# SparkFun_MAX30101_Qwiic.net
KiCad netlist of a schematic drawn in EAGLE
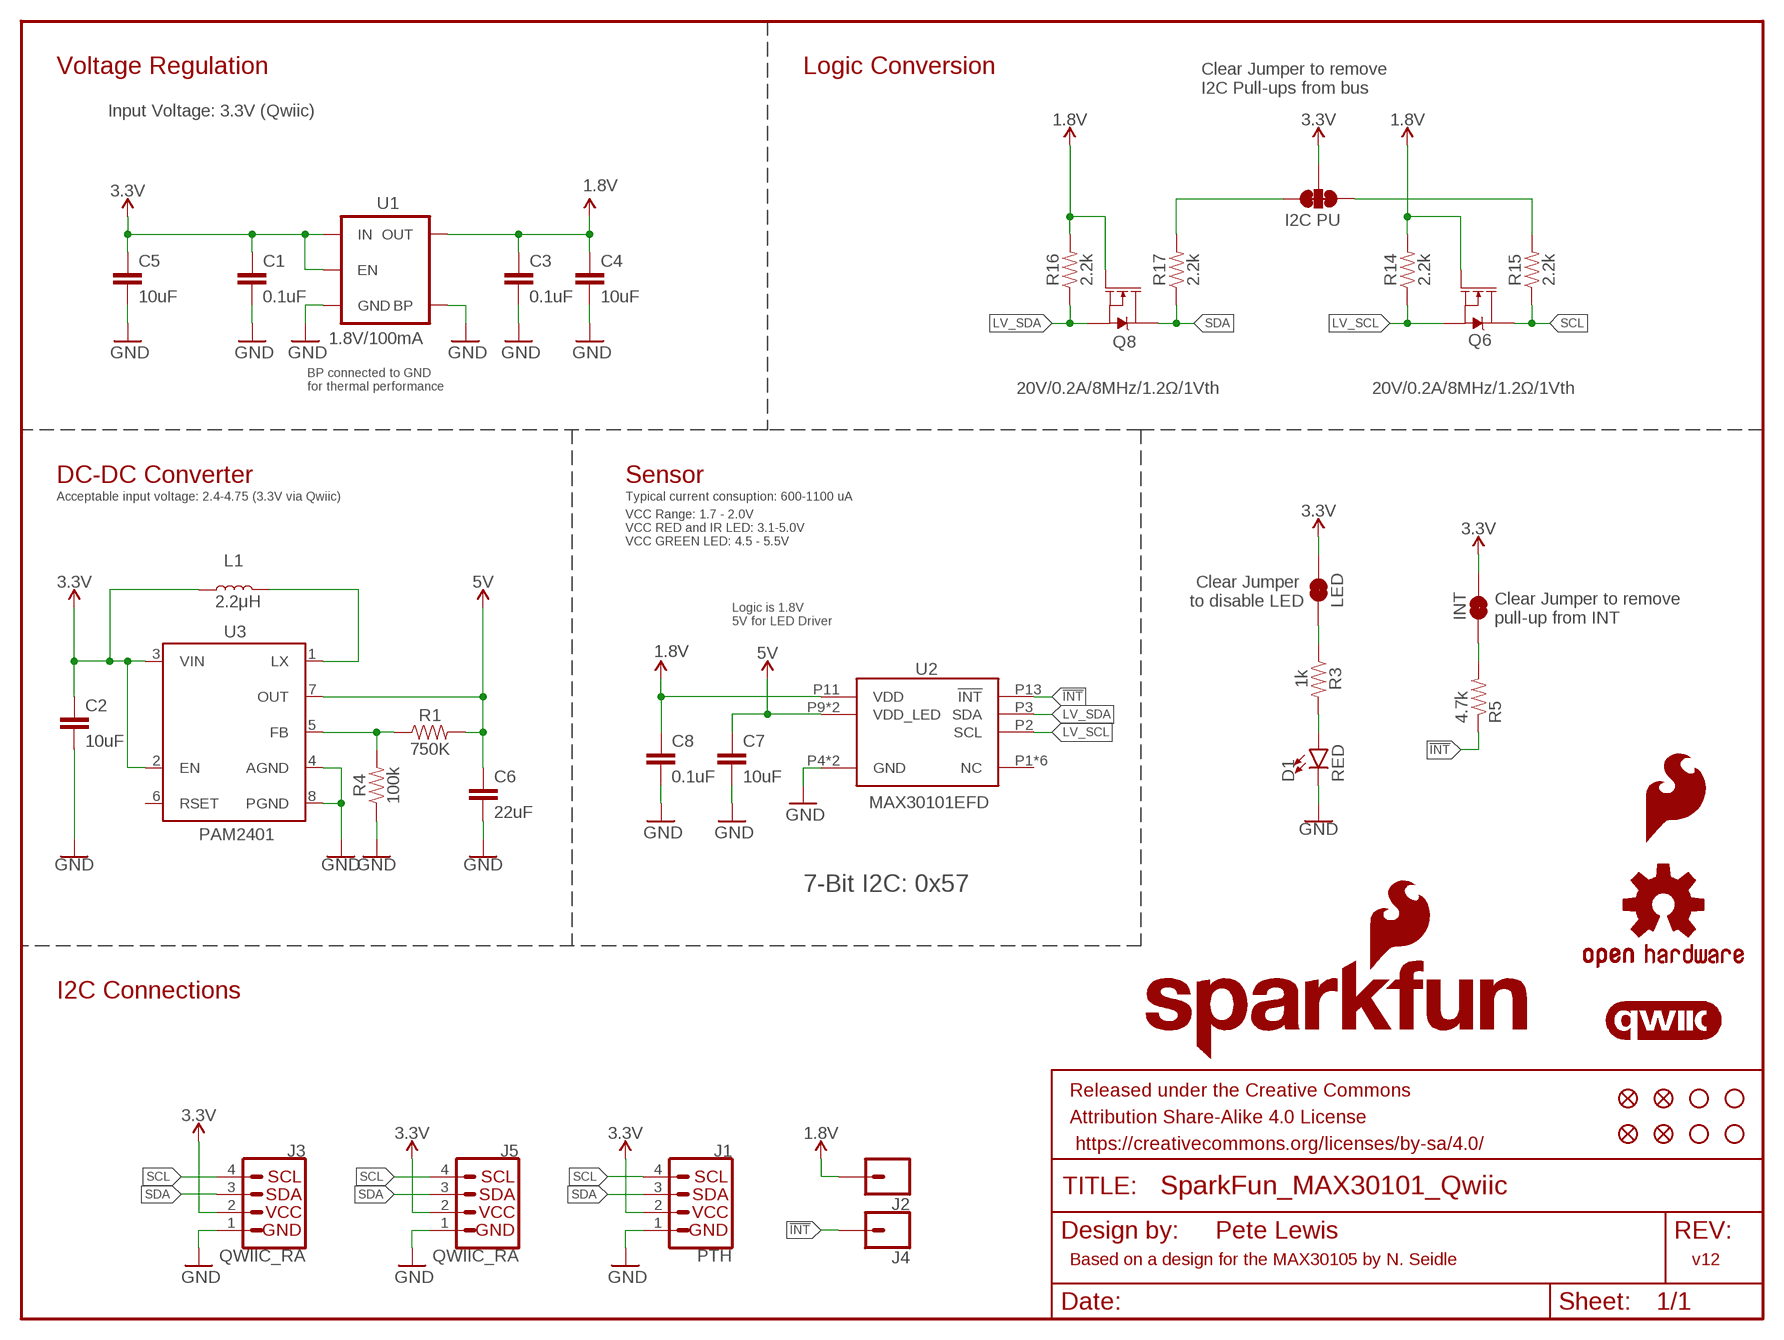
[diagram p0: schematic, sheet 1]

(export (version "E")
  (design (tool "Eeschema 10.0.6"))
  (components
    (comp (ref "C1")
      (value "0.1uF")
      (footprint "eagle-import:0402")
      (libsource (lib "eagle-import") (part "0.1UF-0402-16V-10%"))
    )
    (comp (ref "C2")
      (value "10uF")
      (footprint "eagle-import:0603")
      (libsource (lib "eagle-import") (part "10UF-0603-6.3V-20%"))
    )
    (comp (ref "C3")
      (value "0.1uF")
      (footprint "eagle-import:0402")
      (libsource (lib "eagle-import") (part "0.1UF-0402-16V-10%"))
    )
    (comp (ref "C4")
      (value "10uF")
      (footprint "eagle-import:0603")
      (libsource (lib "eagle-import") (part "10UF-0603-6.3V-20%"))
    )
    (comp (ref "C5")
      (value "10uF")
      (footprint "eagle-import:0603")
      (libsource (lib "eagle-import") (part "10UF-0603-6.3V-20%"))
    )
    (comp (ref "C6")
      (value "22uF")
      (footprint "eagle-import:0805")
      (libsource (lib "eagle-import") (part "22UF-0805-6.3V-20%"))
    )
    (comp (ref "C7")
      (value "10uF")
      (footprint "eagle-import:0603")
      (libsource (lib "eagle-import") (part "10UF-0603-6.3V-20%"))
    )
    (comp (ref "C8")
      (value "0.1uF")
      (footprint "eagle-import:0402")
      (libsource (lib "eagle-import") (part "0.1UF-0402-16V-10%"))
    )
    (comp (ref "D1")
      (value "RED")
      (footprint "eagle-import:LED-0603")
      (libsource (lib "eagle-import") (part "LED-RED0603"))
    )
    (comp (ref "FID1")
      (value "FIDUCIAL1X2")
      (footprint "eagle-import:FIDUCIAL-1X2")
      (libsource (lib "eagle-import") (part "FIDUCIAL1X2"))
    )
    (comp (ref "FID2")
      (value "FIDUCIAL1X2")
      (footprint "eagle-import:FIDUCIAL-1X2")
      (libsource (lib "eagle-import") (part "FIDUCIAL1X2"))
    )
    (comp (ref "FID3")
      (value "FIDUCIAL1X2")
      (footprint "eagle-import:FIDUCIAL-1X2")
      (libsource (lib "eagle-import") (part "FIDUCIAL1X2"))
    )
    (comp (ref "FID4")
      (value "FIDUCIAL1X2")
      (footprint "eagle-import:FIDUCIAL-1X2")
      (libsource (lib "eagle-import") (part "FIDUCIAL1X2"))
    )
    (comp (ref "FRAME1")
      (value "FRAME-LETTER")
      (footprint "eagle-import:CREATIVE_COMMONS")
      (libsource (lib "eagle-import") (part "FRAME-LETTER"))
    )
    (comp (ref "J1")
      (value "PTH")
      (footprint "eagle-import:1X04_NO_SILK")
      (libsource (lib "eagle-import") (part "I2C_STANDARD_NO_SILK"))
    )
    (comp (ref "J2")
      (value "CONN_01PTH_NO_SILK_YES_STOP")
      (footprint "eagle-import:1X01_NO_SILK")
      (libsource (lib "eagle-import") (part "CONN_01PTH_NO_SILK_YES_STOP"))
    )
    (comp (ref "J3")
      (value "QWIIC_RA")
      (footprint "eagle-import:JST04_1MM_RA")
      (libsource (lib "eagle-import") (part "QWIIC_CONNECTORJS-1MM"))
    )
    (comp (ref "J4")
      (value "CONN_01PTH_NO_SILK_YES_STOP")
      (footprint "eagle-import:1X01_NO_SILK")
      (libsource (lib "eagle-import") (part "CONN_01PTH_NO_SILK_YES_STOP"))
    )
    (comp (ref "J5")
      (value "QWIIC_RA")
      (footprint "eagle-import:JST04_1MM_RA")
      (libsource (lib "eagle-import") (part "QWIIC_CONNECTORJS-1MM"))
    )
    (comp (ref "JP1")
      (value "LED")
      (footprint "eagle-import:SMT-JUMPER_2_NC_TRACE_SILK")
      (libsource (lib "eagle-import") (part "JUMPER-SMT_2_NC_TRACE_SILK"))
    )
    (comp (ref "JP2")
      (value "INT")
      (footprint "eagle-import:SMT-JUMPER_2_NC_TRACE_SILK")
      (libsource (lib "eagle-import") (part "JUMPER-SMT_2_NC_TRACE_SILK"))
    )
    (comp (ref "JP4")
      (value "I2C PU")
      (footprint "eagle-import:SMT-JUMPER_3_2-NC_TRACE_SILK")
      (libsource (lib "eagle-import") (part "JUMPER-SMT_3_2-NC_TRACE_SILK"))
    )
    (comp (ref "L1")
      (value "2.2μH")
      (footprint "eagle-import:0806")
      (libsource (lib "eagle-import") (part "2.2μH_SHIELDED_INDUCTOR"))
    )
    (comp (ref "LOGO1")
      (value "SFE_LOGO_NAME_FLAME.1_INCH")
      (footprint "eagle-import:SFE_LOGO_NAME_FLAME_.1")
      (libsource (lib "eagle-import") (part "SFE_LOGO_NAME_FLAME.1_INCH"))
    )
    (comp (ref "LOGO2")
      (value "OSHW-LOGOS")
      (footprint "eagle-import:OSHW-LOGO-S")
      (libsource (lib "eagle-import") (part "OSHW-LOGOS"))
    )
    (comp (ref "LOGO3")
      (value "QWIIC_LOGO_5MM")
      (footprint "eagle-import:QWIIC_5MM")
      (libsource (lib "eagle-import") (part "QWIIC_LOGO_5MM"))
    )
    (comp (ref "LOGO4")
      (value "SFE_LOGO_FLAME.1_INCH")
      (footprint "eagle-import:SFE_LOGO_FLAME_.1")
      (libsource (lib "eagle-import") (part "SFE_LOGO_FLAME.1_INCH"))
    )
    (comp (ref "Q6")
      (value "20V/0.2A/8MHz/1.2Ω/1Vth")
      (footprint "eagle-import:SOT-416FL")
      (libsource (lib "eagle-import") (part "MOSFET-NCH-RE1C00UNTL"))
    )
    (comp (ref "Q8")
      (value "20V/0.2A/8MHz/1.2Ω/1Vth")
      (footprint "eagle-import:SOT-416FL")
      (libsource (lib "eagle-import") (part "MOSFET-NCH-RE1C00UNTL"))
    )
    (comp (ref "R1")
      (value "750K")
      (footprint "eagle-import:0603")
      (libsource (lib "eagle-import") (part "750KOHM-0603-1/10W-1%"))
    )
    (comp (ref "R3")
      (value "1k")
      (footprint "eagle-import:0603")
      (libsource (lib "eagle-import") (part "1KOHM-0603-1/10W-1%"))
    )
    (comp (ref "R4")
      (value "100k")
      (footprint "eagle-import:0603")
      (libsource (lib "eagle-import") (part "100KOHM-0603-1/10W-1%"))
    )
    (comp (ref "R5")
      (value "4.7k")
      (footprint "eagle-import:0603")
      (libsource (lib "eagle-import") (part "4.7KOHM-0603-1/10W-1%"))
    )
    (comp (ref "R14")
      (value "2.2k")
      (footprint "eagle-import:0603")
      (libsource (lib "eagle-import") (part "2.2KOHM-0603-1/10W-1%"))
    )
    (comp (ref "R15")
      (value "2.2k")
      (footprint "eagle-import:0603")
      (libsource (lib "eagle-import") (part "2.2KOHM-0603-1/10W-1%"))
    )
    (comp (ref "R16")
      (value "2.2k")
      (footprint "eagle-import:0603")
      (libsource (lib "eagle-import") (part "2.2KOHM-0603-1/10W-1%"))
    )
    (comp (ref "R17")
      (value "2.2k")
      (footprint "eagle-import:0603")
      (libsource (lib "eagle-import") (part "2.2KOHM-0603-1/10W-1%"))
    )
    (comp (ref "STANDOFF1")
      (value "STAND-OFF")
      (footprint "eagle-import:STAND-OFF")
      (libsource (lib "eagle-import") (part "STAND-OFF"))
    )
    (comp (ref "STANDOFF2")
      (value "STAND-OFF")
      (footprint "eagle-import:STAND-OFF")
      (libsource (lib "eagle-import") (part "STAND-OFF"))
    )
    (comp (ref "STANDOFF3")
      (value "STAND-OFF")
      (footprint "eagle-import:STAND-OFF")
      (libsource (lib "eagle-import") (part "STAND-OFF"))
    )
    (comp (ref "STANDOFF4")
      (value "STAND-OFF")
      (footprint "eagle-import:STAND-OFF")
      (libsource (lib "eagle-import") (part "STAND-OFF"))
    )
    (comp (ref "U1")
      (value "1.8V/100mA")
      (footprint "eagle-import:SC70")
      (libsource (lib "eagle-import") (part "V_REG_SP62141.8V"))
    )
    (comp (ref "U2")
      (value "MAX30101EFD")
      (footprint "eagle-import:14_PIN_OESIP")
      (libsource (lib "eagle-import") (part "MAX30101EFD"))
    )
    (comp (ref "U3")
      (value "PAM2401")
      (footprint "eagle-import:MSOP8")
      (libsource (lib "eagle-import") (part "PAM2401"))
    )
  )
  (nets
    (net (code "1") (name "/~{INT}") (class "Default")
      (node (ref "J4") (pin "1") (pinfunction "1_1") (pintype "passive"))
      (node (ref "R5") (pin "1") (pinfunction "1_1") (pintype "passive"))
      (node (ref "U2") (pin "P13") (pinfunction "~{INT}_P13") (pintype "bidirectional"))
    )
    (net (code "2") (name "1.8V") (class "Default")
      (node (ref "C3") (pin "1") (pinfunction "1_1") (pintype "passive"))
      (node (ref "C4") (pin "1") (pinfunction "1_1") (pintype "passive"))
      (node (ref "C8") (pin "1") (pinfunction "1_1") (pintype "passive"))
      (node (ref "J2") (pin "1") (pinfunction "1_1") (pintype "passive"))
      (node (ref "Q6") (pin "1") (pinfunction "G_1") (pintype "bidirectional"))
      (node (ref "Q8") (pin "1") (pinfunction "G_1") (pintype "bidirectional"))
      (node (ref "R14") (pin "2") (pinfunction "2_2") (pintype "passive"))
      (node (ref "R16") (pin "2") (pinfunction "2_2") (pintype "passive"))
      (node (ref "U1") (pin "5") (pinfunction "OUT_5") (pintype "passive"))
      (node (ref "U2") (pin "P11") (pinfunction "VDD_P11") (pintype "power_in"))
    )
    (net (code "3") (name "3.3V") (class "Default")
      (node (ref "C1") (pin "1") (pinfunction "1_1") (pintype "passive"))
      (node (ref "C2") (pin "1") (pinfunction "1_1") (pintype "passive"))
      (node (ref "C5") (pin "1") (pinfunction "1_1") (pintype "passive"))
      (node (ref "J1") (pin "2") (pinfunction "2_2") (pintype "power_in"))
      (node (ref "J3") (pin "2") (pinfunction "2_2") (pintype "power_in"))
      (node (ref "J5") (pin "2") (pinfunction "2_2") (pintype "power_in"))
      (node (ref "JP1") (pin "2") (pinfunction "2_2") (pintype "passive"))
      (node (ref "JP2") (pin "2") (pinfunction "2_2") (pintype "passive"))
      (node (ref "JP4") (pin "2") (pinfunction "2_2") (pintype "passive"))
      (node (ref "L1") (pin "1") (pinfunction "1_1") (pintype "passive"))
      (node (ref "U1") (pin "1") (pinfunction "IN_1") (pintype "input"))
      (node (ref "U1") (pin "3") (pinfunction "EN_3") (pintype "input"))
      (node (ref "U3") (pin "2") (pinfunction "EN_2") (pintype "bidirectional"))
      (node (ref "U3") (pin "3") (pinfunction "VIN_3") (pintype "bidirectional"))
    )
    (net (code "4") (name "5V") (class "Default")
      (node (ref "C6") (pin "1") (pinfunction "1_1") (pintype "passive"))
      (node (ref "C7") (pin "1") (pinfunction "1_1") (pintype "passive"))
      (node (ref "R1") (pin "2") (pinfunction "2_2") (pintype "passive"))
      (node (ref "U2") (pin "P10") (pinfunction "VDD_LED_P10") (pintype "power_in"))
      (node (ref "U2") (pin "P9") (pinfunction "VDD_LED_P9") (pintype "power_in"))
      (node (ref "U3") (pin "7") (pinfunction "OUT_7") (pintype "bidirectional"))
    )
    (net (code "5") (name "GND") (class "Default")
      (node (ref "C1") (pin "2") (pinfunction "2_2") (pintype "passive"))
      (node (ref "C2") (pin "2") (pinfunction "2_2") (pintype "passive"))
      (node (ref "C3") (pin "2") (pinfunction "2_2") (pintype "passive"))
      (node (ref "C4") (pin "2") (pinfunction "2_2") (pintype "passive"))
      (node (ref "C5") (pin "2") (pinfunction "2_2") (pintype "passive"))
      (node (ref "C6") (pin "2") (pinfunction "2_2") (pintype "passive"))
      (node (ref "C7") (pin "2") (pinfunction "2_2") (pintype "passive"))
      (node (ref "C8") (pin "2") (pinfunction "2_2") (pintype "passive"))
      (node (ref "D1") (pin "C") (pinfunction "C_C") (pintype "passive"))
      (node (ref "J1") (pin "1") (pinfunction "1_1") (pintype "power_in"))
      (node (ref "J3") (pin "1") (pinfunction "1_1") (pintype "power_in"))
      (node (ref "J5") (pin "1") (pinfunction "1_1") (pintype "power_in"))
      (node (ref "R4") (pin "1") (pinfunction "1_1") (pintype "passive"))
      (node (ref "U1") (pin "2") (pinfunction "GND_2") (pintype "input"))
      (node (ref "U1") (pin "4") (pinfunction "BP_4") (pintype "input"))
      (node (ref "U2") (pin "P12") (pinfunction "GND_P12") (pintype "power_in"))
      (node (ref "U2") (pin "P4") (pinfunction "GND_P4") (pintype "power_in"))
      (node (ref "U3") (pin "4") (pinfunction "AGND_4") (pintype "bidirectional"))
      (node (ref "U3") (pin "8") (pinfunction "PGND_8") (pintype "bidirectional"))
    )
    (net (code "6") (name "LV_SCL") (class "Default")
      (node (ref "Q6") (pin "2") (pinfunction "S_2") (pintype "bidirectional"))
      (node (ref "R14") (pin "1") (pinfunction "1_1") (pintype "passive"))
      (node (ref "U2") (pin "P2") (pinfunction "SCL_P2") (pintype "bidirectional"))
    )
    (net (code "7") (name "LV_SDA") (class "Default")
      (node (ref "Q8") (pin "2") (pinfunction "S_2") (pintype "bidirectional"))
      (node (ref "R16") (pin "1") (pinfunction "1_1") (pintype "passive"))
      (node (ref "U2") (pin "P3") (pinfunction "SDA_P3") (pintype "bidirectional"))
    )
    (net (code "8") (name "Net-(D1-PadA)") (class "Default")
      (node (ref "D1") (pin "A") (pinfunction "A_A") (pintype "passive"))
      (node (ref "R3") (pin "2") (pinfunction "2_2") (pintype "passive"))
    )
    (net (code "9") (name "Net-(JP1-Pad1)") (class "Default")
      (node (ref "JP1") (pin "1") (pinfunction "1_1") (pintype "passive"))
      (node (ref "R3") (pin "1") (pinfunction "1_1") (pintype "passive"))
    )
    (net (code "10") (name "Net-(JP2-Pad1)") (class "Default")
      (node (ref "JP2") (pin "1") (pinfunction "1_1") (pintype "passive"))
      (node (ref "R5") (pin "2") (pinfunction "2_2") (pintype "passive"))
    )
    (net (code "11") (name "Net-(JP4-Pad1)") (class "Default")
      (node (ref "JP4") (pin "1") (pinfunction "1_1") (pintype "passive"))
      (node (ref "R17") (pin "2") (pinfunction "2_2") (pintype "passive"))
    )
    (net (code "12") (name "Net-(JP4-Pad3)") (class "Default")
      (node (ref "JP4") (pin "3") (pinfunction "3_3") (pintype "passive"))
      (node (ref "R15") (pin "2") (pinfunction "2_2") (pintype "passive"))
    )
    (net (code "13") (name "Net-(U3-FB)") (class "Default")
      (node (ref "R1") (pin "1") (pinfunction "1_1") (pintype "passive"))
      (node (ref "R4") (pin "2") (pinfunction "2_2") (pintype "passive"))
      (node (ref "U3") (pin "5") (pinfunction "FB_5") (pintype "bidirectional"))
    )
    (net (code "14") (name "Net-(U3-LX)") (class "Default")
      (node (ref "L1") (pin "2") (pinfunction "2_2") (pintype "passive"))
      (node (ref "U3") (pin "1") (pinfunction "LX_1") (pintype "bidirectional"))
    )
    (net (code "15") (name "SCL") (class "Default")
      (node (ref "J1") (pin "4") (pinfunction "4_4") (pintype "passive"))
      (node (ref "J3") (pin "4") (pinfunction "4_4") (pintype "passive"))
      (node (ref "J5") (pin "4") (pinfunction "4_4") (pintype "passive"))
      (node (ref "Q6") (pin "3") (pinfunction "D_3") (pintype "bidirectional"))
      (node (ref "R15") (pin "1") (pinfunction "1_1") (pintype "passive"))
    )
    (net (code "16") (name "SDA") (class "Default")
      (node (ref "J1") (pin "3") (pinfunction "3_3") (pintype "passive"))
      (node (ref "J3") (pin "3") (pinfunction "3_3") (pintype "passive"))
      (node (ref "J5") (pin "3") (pinfunction "3_3") (pintype "passive"))
      (node (ref "Q8") (pin "3") (pinfunction "D_3") (pintype "bidirectional"))
      (node (ref "R17") (pin "1") (pinfunction "1_1") (pintype "passive"))
    )
    (net (code "17") (name "unconnected-(U2-NC-PadP1)") (class "Default")
      (node (ref "U2") (pin "P1") (pinfunction "NC_P1") (pintype "no_connect"))
    )
    (net (code "18") (name "unconnected-(U2-NC-PadP5)") (class "Default")
      (node (ref "U2") (pin "P5") (pinfunction "NC_P5") (pintype "no_connect"))
    )
    (net (code "19") (name "unconnected-(U2-NC-PadP6)") (class "Default")
      (node (ref "U2") (pin "P6") (pinfunction "NC_P6") (pintype "no_connect"))
    )
    (net (code "20") (name "unconnected-(U2-NC-PadP7)") (class "Default")
      (node (ref "U2") (pin "P7") (pinfunction "NC_P7") (pintype "no_connect"))
    )
    (net (code "21") (name "unconnected-(U2-NC-PadP8)") (class "Default")
      (node (ref "U2") (pin "P8") (pinfunction "NC_P8") (pintype "no_connect"))
    )
    (net (code "22") (name "unconnected-(U2-NC-PadP14)") (class "Default")
      (node (ref "U2") (pin "P14") (pinfunction "NC_P14") (pintype "no_connect"))
    )
    (net (code "23") (name "unconnected-(U3-RSET-Pad6)") (class "Default")
      (node (ref "U3") (pin "6") (pinfunction "RSET_6") (pintype "bidirectional"))
    )
  )
)
